# tiny_base_21_21.net
KiCad netlist of a schematic drawn in EAGLE
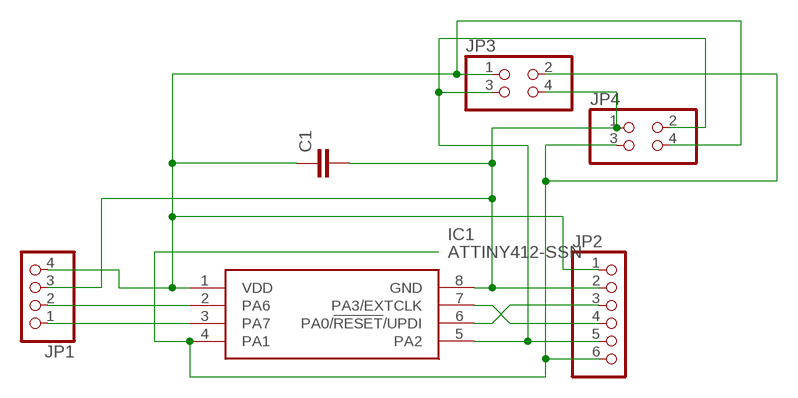
[diagram p0: schematic, sheet 1]

(export (version "E")
  (design (tool "Eeschema 10.0.6"))
  (components
    (comp (ref "C1")
      (value "C-EUC0805K")
      (footprint "eagle-import:C0805K")
      (libsource (lib "eagle-import") (part "C-EUC0805K"))
    )
    (comp (ref "IC1")
      (value "ATTINY412-SSN")
      (footprint "eagle-import:SOIC127P600X175-8N")
      (fields (field (name "MOUSER_PART_NUMBER") "579-ATTINY412-SSN"))
      (libsource (lib "eagle-import") (part "ATTINY412-SSN"))
    )
    (comp (ref "JP1")
      (value "PINHD-1X4")
      (footprint "eagle-import:1X04")
      (libsource (lib "eagle-import") (part "PINHD-1X4"))
    )
    (comp (ref "JP2")
      (value "PINHD-1X6")
      (footprint "eagle-import:1X06")
      (libsource (lib "eagle-import") (part "PINHD-1X6"))
    )
    (comp (ref "JP3")
      (value "PINHD-2X2")
      (footprint "eagle-import:2X02")
      (libsource (lib "eagle-import") (part "PINHD-2X2"))
    )
    (comp (ref "JP4")
      (value "PINHD-2X2")
      (footprint "eagle-import:2X02")
      (libsource (lib "eagle-import") (part "PINHD-2X2"))
    )
  )
  (nets
    (net (code "1") (name "Net-(IC1-GND)") (class "Default")
      (node (ref "C1") (pin "2") (pinfunction "2_2") (pintype "passive"))
      (node (ref "IC1") (pin "8") (pinfunction "GND_8") (pintype "bidirectional"))
      (node (ref "JP1") (pin "3") (pinfunction "3_3") (pintype "passive"))
      (node (ref "JP2") (pin "2") (pinfunction "2_2") (pintype "passive"))
      (node (ref "JP3") (pin "4") (pinfunction "4_4") (pintype "passive"))
      (node (ref "JP4") (pin "1") (pinfunction "1_1") (pintype "passive"))
    )
    (net (code "2") (name "Net-(IC1-PA0{slash}~{RESET}{slash}UPDI)") (class "Default")
      (node (ref "IC1") (pin "6") (pinfunction "PA0/~{RESET}/UPDI_6") (pintype "bidirectional"))
      (node (ref "JP2") (pin "3") (pinfunction "3_3") (pintype "passive"))
    )
    (net (code "3") (name "Net-(IC1-PA1)") (class "Default")
      (node (ref "IC1") (pin "4") (pinfunction "PA1_4") (pintype "bidirectional"))
      (node (ref "JP2") (pin "6") (pinfunction "6_6") (pintype "passive"))
      (node (ref "JP3") (pin "2") (pinfunction "2_2") (pintype "passive"))
      (node (ref "JP4") (pin "3") (pinfunction "3_3") (pintype "passive"))
    )
    (net (code "4") (name "Net-(IC1-PA2)") (class "Default")
      (node (ref "IC1") (pin "5") (pinfunction "PA2_5") (pintype "bidirectional"))
      (node (ref "JP2") (pin "5") (pinfunction "5_5") (pintype "passive"))
      (node (ref "JP3") (pin "3") (pinfunction "3_3") (pintype "passive"))
      (node (ref "JP4") (pin "2") (pinfunction "2_2") (pintype "passive"))
    )
    (net (code "5") (name "Net-(IC1-PA3{slash}EXTCLK)") (class "Default")
      (node (ref "IC1") (pin "7") (pinfunction "PA3/EXTCLK_7") (pintype "bidirectional"))
      (node (ref "JP2") (pin "4") (pinfunction "4_4") (pintype "passive"))
    )
    (net (code "6") (name "Net-(IC1-PA6)") (class "Default")
      (node (ref "IC1") (pin "2") (pinfunction "PA6_2") (pintype "bidirectional"))
      (node (ref "JP1") (pin "2") (pinfunction "2_2") (pintype "passive"))
    )
    (net (code "7") (name "Net-(IC1-PA7)") (class "Default")
      (node (ref "IC1") (pin "3") (pinfunction "PA7_3") (pintype "bidirectional"))
      (node (ref "JP1") (pin "1") (pinfunction "1_1") (pintype "passive"))
    )
    (net (code "8") (name "Net-(IC1-VDD)") (class "Default")
      (node (ref "C1") (pin "1") (pinfunction "1_1") (pintype "passive"))
      (node (ref "IC1") (pin "1") (pinfunction "VDD_1") (pintype "bidirectional"))
      (node (ref "JP1") (pin "4") (pinfunction "4_4") (pintype "passive"))
      (node (ref "JP2") (pin "1") (pinfunction "1_1") (pintype "passive"))
      (node (ref "JP3") (pin "1") (pinfunction "1_1") (pintype "passive"))
      (node (ref "JP4") (pin "4") (pinfunction "4_4") (pintype "passive"))
    )
  )
)
